# Flash.net
KiCad netlist of a schematic drawn in Altium Designer
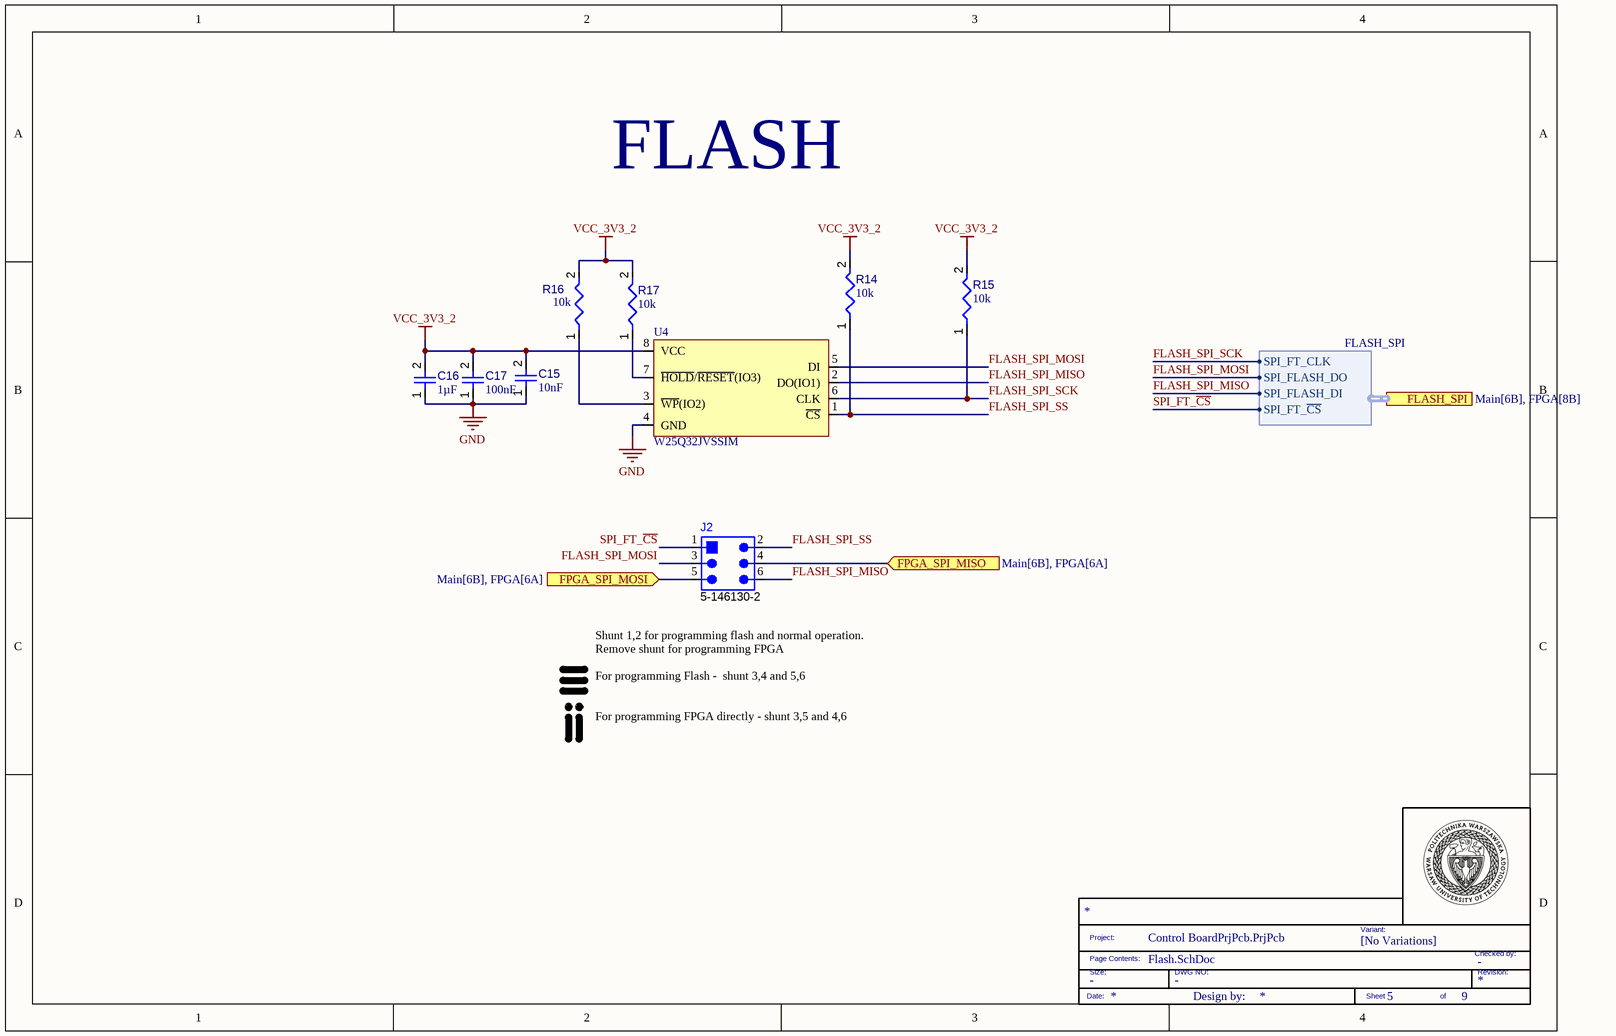
[diagram p0: Flash.SchDoc]

(export (version "E")
  (design (tool "Eeschema 10.0.6"))
  (components
    (comp (ref "C15")
      (value "10nF")
      (footprint "CAPC1608X90X35LL10T15")
      (fields (field (name "TOLERANCE") "10%") (field (name "Comment") "GCM188R71H103KA37J"))
      (libsource (lib "Warsaw University of Technology") (part "CAP-NP-2"))
    )
    (comp (ref "C16")
      (value "1µF")
      (footprint "FP-CL10-IPC_C")
      (fields (field (name "Comment") "CL10B105KA8NFNC"))
      (libsource (lib "Warsaw University of Technology") (part "CAP-NP-2"))
    )
    (comp (ref "C17")
      (value "100nF")
      (footprint "FP-C0603C-CF-IPC_C")
      (fields (field (name "Comment") "C0603C104K5RAC7411"))
      (libsource (lib "Warsaw University of Technology") (part "CAP-NP-2"))
    )
    (comp (ref "J2")
      (value "5-146130-2")
      (footprint "TECO-5-146130-2_V")
      (description "Male Header, Pitch 2.54 mm, 2 x 3 Position, Height 8.13 mm, -65 to 125 degC, RoHS, Tube")
      (fields (field (name "MANUFACTURER") "TE Connectivity"))
      (libsource (lib "Warsaw University of Technology") (part "CN-2P-M-R6"))
    )
    (comp (ref "R14")
      (value "10k")
      (footprint "RESC1608X05N")
      (fields
        (field (name "TOLERANCE") "1%")
        (field (name "POWER") "100mW")
        (field (name "Comment") "CRCW060310K0FKTC")
      )
      (libsource (lib "Warsaw University of Technology") (part "RES-2"))
    )
    (comp (ref "R15")
      (value "10k")
      (footprint "RESC1608X05N")
      (fields
        (field (name "TOLERANCE") "1%")
        (field (name "POWER") "100mW")
        (field (name "Comment") "CRCW060310K0FKTC")
      )
      (libsource (lib "Warsaw University of Technology") (part "RES-2"))
    )
    (comp (ref "R16")
      (value "10k")
      (footprint "RESC1608X05N")
      (fields
        (field (name "TOLERANCE") "1%")
        (field (name "POWER") "100mW")
        (field (name "Comment") "CRCW060310K0FKTC")
      )
      (libsource (lib "Warsaw University of Technology") (part "RES-2"))
    )
    (comp (ref "R17")
      (value "10k")
      (footprint "RESC1608X05N")
      (fields
        (field (name "TOLERANCE") "1%")
        (field (name "POWER") "100mW")
        (field (name "Comment") "CRCW060310K0FKTC")
      )
      (libsource (lib "Warsaw University of Technology") (part "RES-2"))
    )
    (comp (ref "U4")
      (value "W25Q32JVSSIM")
      (footprint "SOIC127P790X175-8N")
      (description "Flash, 4MX8, PDSO8")
      (libsource (lib "Warsaw University of Technology") (part "W25Q32JVSSIM-Symbol-1"))
    )
  )
  (nets
    (net (code "2") (name "/FLASH_SPI_MISO") (class "Default")
      (node (ref "J2") (pin "6") (pinfunction "6_6") (pintype "passive"))
      (node (ref "U4") (pin "2") (pinfunction "DO(IO1)_2") (pintype "passive"))
    )
    (net (code "3") (name "/FLASH_SPI_MOSI") (class "Default")
      (node (ref "J2") (pin "3") (pinfunction "3_3") (pintype "passive"))
      (node (ref "U4") (pin "5") (pinfunction "DI_5") (pintype "passive"))
    )
    (net (code "4") (name "/FLASH_SPI_SCK") (class "Default")
      (node (ref "R15") (pin "1") (pinfunction "1_1") (pintype "passive"))
      (node (ref "U4") (pin "6") (pinfunction "CLK_6") (pintype "passive"))
    )
    (net (code "5") (name "/FLASH_SPI_SS") (class "Default")
      (node (ref "J2") (pin "2") (pinfunction "2_2") (pintype "passive"))
      (node (ref "R14") (pin "1") (pinfunction "1_1") (pintype "passive"))
      (node (ref "U4") (pin "1") (pinfunction "~{CS}_1") (pintype "passive"))
    )
    (net (code "6") (name "/FPGA_SPI_MISO") (class "Default")
      (node (ref "J2") (pin "4") (pinfunction "4_4") (pintype "passive"))
    )
    (net (code "7") (name "/FPGA_SPI_MOSI") (class "Default")
      (node (ref "J2") (pin "5") (pinfunction "5_5") (pintype "passive"))
    )
    (net (code "8") (name "/SPI_FT_~{CS}") (class "Default")
      (node (ref "J2") (pin "1") (pinfunction "1_1") (pintype "passive"))
    )
    (net (code "10") (name "GND") (class "Default")
      (node (ref "C15") (pin "1") (pinfunction "1_1") (pintype "passive"))
      (node (ref "C16") (pin "1") (pinfunction "1_1") (pintype "passive"))
      (node (ref "C17") (pin "1") (pinfunction "1_1") (pintype "passive"))
      (node (ref "U4") (pin "4") (pinfunction "GND_4") (pintype "passive"))
    )
    (net (code "11") (name "Net-(U4-~{HOLD}{slash}~{RESET}(IO3))") (class "Default")
      (node (ref "R17") (pin "1") (pinfunction "1_1") (pintype "passive"))
      (node (ref "U4") (pin "7") (pinfunction "~{HOLD}/~{RESET}(IO3)_7") (pintype "passive"))
    )
    (net (code "12") (name "Net-(U4-~{WP}(IO2))") (class "Default")
      (node (ref "R16") (pin "1") (pinfunction "1_1") (pintype "passive"))
      (node (ref "U4") (pin "3") (pinfunction "~{WP}(IO2)_3") (pintype "passive"))
    )
    (net (code "13") (name "VCC_3V3_2") (class "Default")
      (node (ref "C15") (pin "2") (pinfunction "2_2") (pintype "passive"))
      (node (ref "C16") (pin "2") (pinfunction "2_2") (pintype "passive"))
      (node (ref "C17") (pin "2") (pinfunction "2_2") (pintype "passive"))
      (node (ref "R14") (pin "2") (pinfunction "2_2") (pintype "passive"))
      (node (ref "R15") (pin "2") (pinfunction "2_2") (pintype "passive"))
      (node (ref "R16") (pin "2") (pinfunction "2_2") (pintype "passive"))
      (node (ref "R17") (pin "2") (pinfunction "2_2") (pintype "passive"))
      (node (ref "U4") (pin "8") (pinfunction "VCC_8") (pintype "passive"))
    )
  )
)
